# MCU.net
KiCad netlist of a schematic drawn in Altium Designer
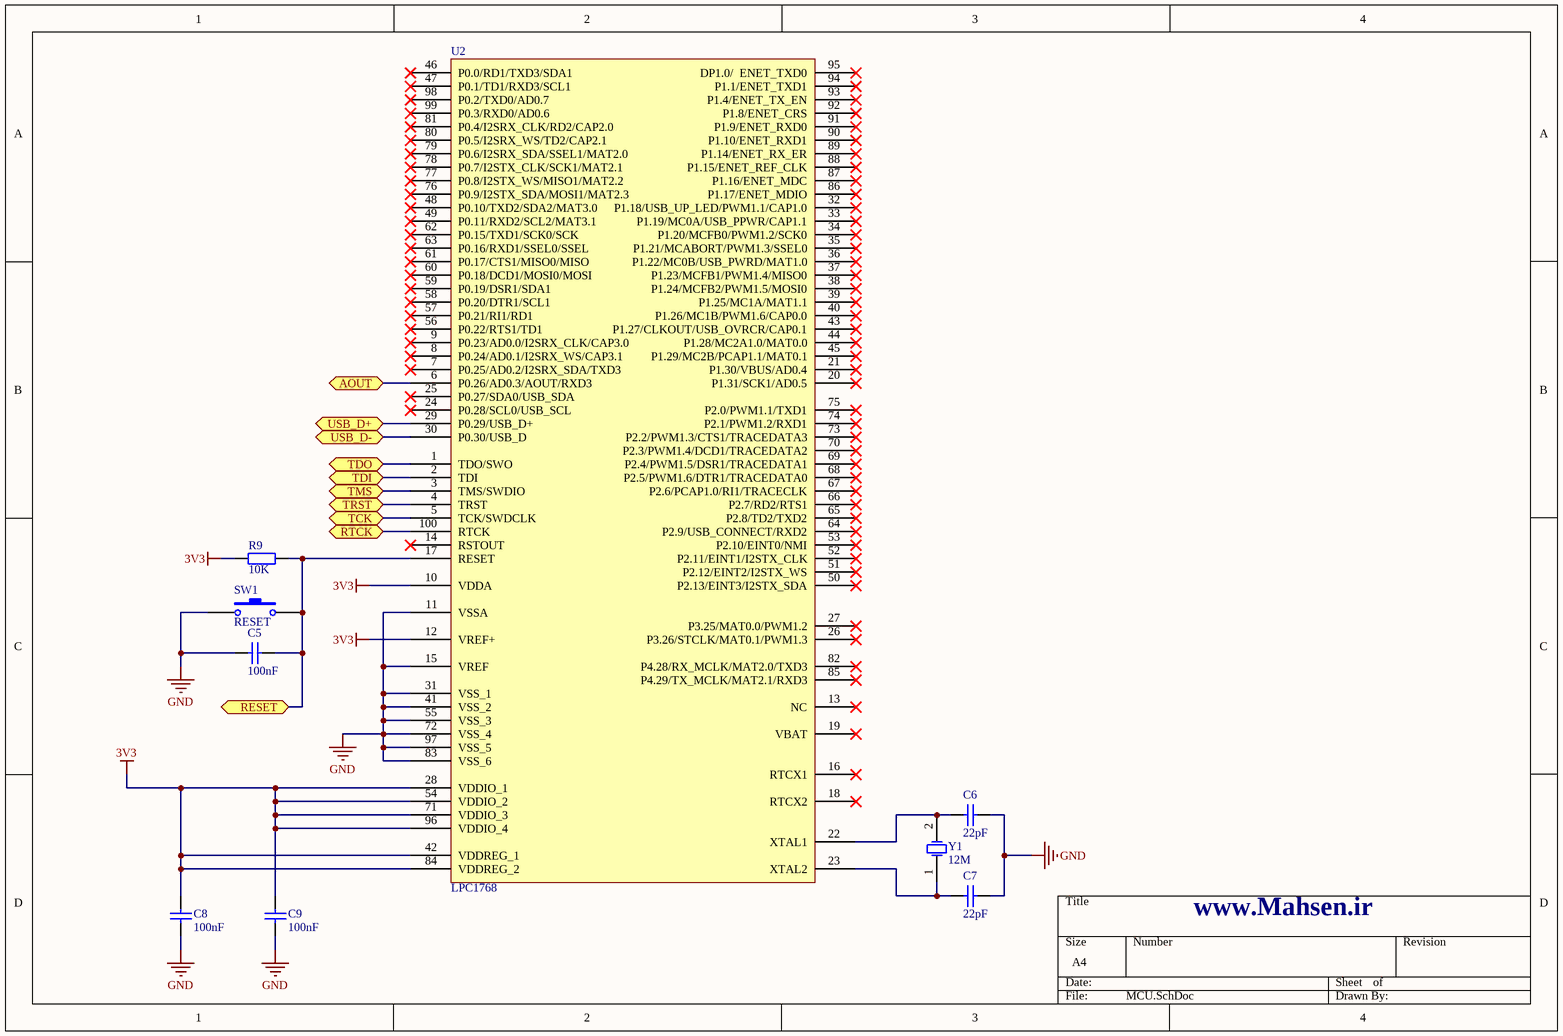
[diagram p0: MCU.SchDoc]

(export (version "E")
  (design (tool "Eeschema 10.0.6"))
  (components
    (comp (ref "C5")
      (value "100nF")
      (footprint "0805")
      (description "Capacitor")
      (fields (field (name "PUBLISHER") "Altium Limited"))
      (libsource (lib "Miscellaneous Devices") (part "Cap"))
    )
    (comp (ref "C6")
      (value "22pF")
      (footprint "0805")
      (description "Capacitor")
      (fields (field (name "PUBLISHER") "Altium Limited"))
      (libsource (lib "Miscellaneous Devices") (part "Cap"))
    )
    (comp (ref "C7")
      (value "22pF")
      (footprint "0805")
      (description "Capacitor")
      (fields (field (name "PUBLISHER") "Altium Limited"))
      (libsource (lib "Miscellaneous Devices") (part "Cap"))
    )
    (comp (ref "C8")
      (value "100nF")
      (footprint "0805")
      (description "Capacitor")
      (fields (field (name "PUBLISHER") "Altium Limited"))
      (libsource (lib "Miscellaneous Devices") (part "Cap"))
    )
    (comp (ref "C9")
      (value "100nF")
      (footprint "0805")
      (description "Capacitor")
      (fields (field (name "PUBLISHER") "Altium Limited"))
      (libsource (lib "Miscellaneous Devices") (part "Cap"))
    )
    (comp (ref "R9")
      (value "10K")
      (footprint "0805")
      (description "Resistor")
      (fields (field (name "PUBLISHER") "Altium Limited"))
      (libsource (lib "Miscellaneous Devices") (part "Res2"))
    )
    (comp (ref "SW1")
      (value "RESET")
      (footprint "SPST-2")
      (description "Switch")
      (fields (field (name "PUBLISHER") "Altium Limited"))
      (libsource (lib "Miscellaneous Devices") (part "SW-PB"))
    )
    (comp (ref "U2") (value "LPC1768") (footprint "LQFP_100") (libsource (lib "Lotfi") (part "LPC1768")))
    (comp (ref "Y1")
      (value "12M")
      (footprint "XTALA")
      (description "Crystal Oscillator")
      (fields (field (name "PUBLISHER") "Altium Limited"))
      (libsource (lib "Miscellaneous Devices") (part "XTAL"))
    )
  )
  (nets
    (net (code "1") (name "/AOUT") (class "Default")
      (node (ref "U2") (pin "6") (pinfunction "P0.26/AD0.3/AOUT/RXD3_6") (pintype "passive"))
    )
    (net (code "2") (name "/RESET") (class "Default")
      (node (ref "C5") (pin "1") (pinfunction "1_1") (pintype "passive"))
      (node (ref "R9") (pin "2") (pinfunction "2_2") (pintype "passive"))
      (node (ref "SW1") (pin "2") (pinfunction "2_2") (pintype "passive"))
      (node (ref "U2") (pin "17") (pinfunction "RESET_17") (pintype "passive"))
    )
    (net (code "3") (name "/RTCK") (class "Default")
      (node (ref "U2") (pin "100") (pinfunction "RTCK_100") (pintype "passive"))
    )
    (net (code "4") (name "/TCK") (class "Default")
      (node (ref "U2") (pin "5") (pinfunction "TCK/SWDCLK_5") (pintype "passive"))
    )
    (net (code "5") (name "/TDI") (class "Default")
      (node (ref "U2") (pin "2") (pinfunction "TDI_2") (pintype "passive"))
    )
    (net (code "6") (name "/TDO") (class "Default")
      (node (ref "U2") (pin "1") (pinfunction "TDO/SWO_1") (pintype "passive"))
    )
    (net (code "7") (name "/TMS") (class "Default")
      (node (ref "U2") (pin "3") (pinfunction "TMS/SWDIO_3") (pintype "passive"))
    )
    (net (code "8") (name "/TRST") (class "Default")
      (node (ref "U2") (pin "4") (pinfunction "TRST_4") (pintype "passive"))
    )
    (net (code "9") (name "/USB_D+") (class "Default")
      (node (ref "U2") (pin "29") (pinfunction "P0.29/USB_D+_29") (pintype "passive"))
    )
    (net (code "10") (name "/USB_D-") (class "Default")
      (node (ref "U2") (pin "30") (pinfunction "P0.30/USB_D_30") (pintype "passive"))
    )
    (net (code "11") (name "3V3") (class "Default")
      (node (ref "C8") (pin "1") (pinfunction "1_1") (pintype "passive"))
      (node (ref "C9") (pin "1") (pinfunction "1_1") (pintype "passive"))
      (node (ref "R9") (pin "1") (pinfunction "1_1") (pintype "passive"))
      (node (ref "U2") (pin "10") (pinfunction "VDDA_10") (pintype "passive"))
      (node (ref "U2") (pin "12") (pinfunction "VREF+_12") (pintype "passive"))
      (node (ref "U2") (pin "28") (pinfunction "VDDIO_1_28") (pintype "passive"))
      (node (ref "U2") (pin "42") (pinfunction "VDDREG_1_42") (pintype "passive"))
      (node (ref "U2") (pin "54") (pinfunction "VDDIO_2_54") (pintype "passive"))
      (node (ref "U2") (pin "71") (pinfunction "VDDIO_3_71") (pintype "passive"))
      (node (ref "U2") (pin "84") (pinfunction "VDDREG_2_84") (pintype "passive"))
      (node (ref "U2") (pin "96") (pinfunction "VDDIO_4_96") (pintype "passive"))
    )
    (net (code "12") (name "GND") (class "Default")
      (node (ref "C5") (pin "2") (pinfunction "2_2") (pintype "passive"))
      (node (ref "C6") (pin "2") (pinfunction "2_2") (pintype "passive"))
      (node (ref "C7") (pin "1") (pinfunction "1_1") (pintype "passive"))
      (node (ref "C8") (pin "2") (pinfunction "2_2") (pintype "passive"))
      (node (ref "C9") (pin "2") (pinfunction "2_2") (pintype "passive"))
      (node (ref "SW1") (pin "1") (pinfunction "1_1") (pintype "passive"))
      (node (ref "U2") (pin "11") (pinfunction "VSSA_11") (pintype "passive"))
      (node (ref "U2") (pin "15") (pinfunction "VREF_15") (pintype "passive"))
      (node (ref "U2") (pin "31") (pinfunction "VSS_1_31") (pintype "passive"))
      (node (ref "U2") (pin "41") (pinfunction "VSS_2_41") (pintype "passive"))
      (node (ref "U2") (pin "55") (pinfunction "VSS_3_55") (pintype "passive"))
      (node (ref "U2") (pin "72") (pinfunction "VSS_4_72") (pintype "passive"))
      (node (ref "U2") (pin "83") (pinfunction "VSS_6_83") (pintype "passive"))
      (node (ref "U2") (pin "97") (pinfunction "VSS_5_97") (pintype "passive"))
    )
    (net (code "13") (name "Net-(U2-XTAL1)") (class "Default")
      (node (ref "C6") (pin "1") (pinfunction "1_1") (pintype "passive"))
      (node (ref "U2") (pin "22") (pinfunction "XTAL1_22") (pintype "passive"))
      (node (ref "Y1") (pin "2") (pinfunction "OSC2_2") (pintype "passive"))
    )
    (net (code "14") (name "Net-(U2-XTAL2)") (class "Default")
      (node (ref "C7") (pin "2") (pinfunction "2_2") (pintype "passive"))
      (node (ref "U2") (pin "23") (pinfunction "XTAL2_23") (pintype "passive"))
      (node (ref "Y1") (pin "1") (pinfunction "OSC1_1") (pintype "passive"))
    )
    (net (code "15") (name "unconnected-(U2-DP1.0{slash}__ENET_TXD0-Pad95)") (class "Default")
      (node (ref "U2") (pin "95") (pinfunction "DP1.0/__ENET_TXD0_95") (pintype "passive+no_connect"))
    )
    (net (code "16") (name "unconnected-(U2-NC-Pad13)") (class "Default")
      (node (ref "U2") (pin "13") (pinfunction "NC_13") (pintype "passive+no_connect"))
    )
    (net (code "17") (name "unconnected-(U2-P0.0{slash}RD1{slash}TXD3{slash}SDA1-Pad46)") (class "Default")
      (node (ref "U2") (pin "46") (pinfunction "P0.0/RD1/TXD3/SDA1_46") (pintype "passive+no_connect"))
    )
    (net (code "18") (name "unconnected-(U2-P0.1{slash}TD1{slash}RXD3{slash}SCL1-Pad47)") (class "Default")
      (node (ref "U2") (pin "47") (pinfunction "P0.1/TD1/RXD3/SCL1_47") (pintype "passive+no_connect"))
    )
    (net (code "19") (name "unconnected-(U2-P0.2{slash}TXD0{slash}AD0.7-Pad98)") (class "Default")
      (node (ref "U2") (pin "98") (pinfunction "P0.2/TXD0/AD0.7_98") (pintype "passive+no_connect"))
    )
    (net (code "20") (name "unconnected-(U2-P0.3{slash}RXD0{slash}AD0.6-Pad99)") (class "Default")
      (node (ref "U2") (pin "99") (pinfunction "P0.3/RXD0/AD0.6_99") (pintype "passive+no_connect"))
    )
    (net (code "21") (name "unconnected-(U2-P0.4{slash}I2SRX_CLK{slash}RD2{slash}CAP2.0-Pad81)") (class "Default")
      (node (ref "U2") (pin "81") (pinfunction "P0.4/I2SRX_CLK/RD2/CAP2.0_81") (pintype "passive+no_connect"))
    )
    (net (code "22") (name "unconnected-(U2-P0.5{slash}I2SRX_WS{slash}TD2{slash}CAP2.1-Pad80)") (class "Default")
      (node (ref "U2") (pin "80") (pinfunction "P0.5/I2SRX_WS/TD2/CAP2.1_80") (pintype "passive+no_connect"))
    )
    (net (code "23") (name "unconnected-(U2-P0.6{slash}I2SRX_SDA{slash}SSEL1{slash}MAT2.0-Pad79)") (class "Default")
      (node (ref "U2") (pin "79") (pinfunction "P0.6/I2SRX_SDA/SSEL1/MAT2.0_79") (pintype "passive+no_connect"))
    )
    (net (code "24") (name "unconnected-(U2-P0.7{slash}I2STX_CLK{slash}SCK1{slash}MAT2.1-Pad78)") (class "Default")
      (node (ref "U2") (pin "78") (pinfunction "P0.7/I2STX_CLK/SCK1/MAT2.1_78") (pintype "passive+no_connect"))
    )
    (net (code "25") (name "unconnected-(U2-P0.8{slash}I2STX_WS{slash}MISO1{slash}MAT2.2-Pad77)") (class "Default")
      (node (ref "U2") (pin "77") (pinfunction "P0.8/I2STX_WS/MISO1/MAT2.2_77") (pintype "passive+no_connect"))
    )
    (net (code "26") (name "unconnected-(U2-P0.9{slash}I2STX_SDA{slash}MOSI1{slash}MAT2.3-Pad76)") (class "Default")
      (node (ref "U2") (pin "76") (pinfunction "P0.9/I2STX_SDA/MOSI1/MAT2.3_76") (pintype "passive+no_connect"))
    )
    (net (code "27") (name "unconnected-(U2-P0.10{slash}TXD2{slash}SDA2{slash}MAT3.0-Pad48)") (class "Default")
      (node (ref "U2") (pin "48") (pinfunction "P0.10/TXD2/SDA2/MAT3.0_48") (pintype "passive+no_connect"))
    )
    (net (code "28") (name "unconnected-(U2-P0.11{slash}RXD2{slash}SCL2{slash}MAT3.1-Pad49)") (class "Default")
      (node (ref "U2") (pin "49") (pinfunction "P0.11/RXD2/SCL2/MAT3.1_49") (pintype "passive+no_connect"))
    )
    (net (code "29") (name "unconnected-(U2-P0.15{slash}TXD1{slash}SCK0{slash}SCK-Pad62)") (class "Default")
      (node (ref "U2") (pin "62") (pinfunction "P0.15/TXD1/SCK0/SCK_62") (pintype "passive+no_connect"))
    )
    (net (code "30") (name "unconnected-(U2-P0.16{slash}RXD1{slash}SSEL0{slash}SSEL-Pad63)") (class "Default")
      (node (ref "U2") (pin "63") (pinfunction "P0.16/RXD1/SSEL0/SSEL_63") (pintype "passive+no_connect"))
    )
    (net (code "31") (name "unconnected-(U2-P0.17{slash}CTS1{slash}MISO0{slash}MISO-Pad61)") (class "Default")
      (node (ref "U2") (pin "61") (pinfunction "P0.17/CTS1/MISO0/MISO_61") (pintype "passive+no_connect"))
    )
    (net (code "32") (name "unconnected-(U2-P0.18{slash}DCD1{slash}MOSI0{slash}MOSI-Pad60)") (class "Default")
      (node (ref "U2") (pin "60") (pinfunction "P0.18/DCD1/MOSI0/MOSI_60") (pintype "passive+no_connect"))
    )
    (net (code "33") (name "unconnected-(U2-P0.19{slash}DSR1{slash}SDA1-Pad59)") (class "Default")
      (node (ref "U2") (pin "59") (pinfunction "P0.19/DSR1/SDA1_59") (pintype "passive+no_connect"))
    )
    (net (code "34") (name "unconnected-(U2-P0.20{slash}DTR1{slash}SCL1-Pad58)") (class "Default")
      (node (ref "U2") (pin "58") (pinfunction "P0.20/DTR1/SCL1_58") (pintype "passive+no_connect"))
    )
    (net (code "35") (name "unconnected-(U2-P0.21{slash}RI1{slash}RD1-Pad57)") (class "Default")
      (node (ref "U2") (pin "57") (pinfunction "P0.21/RI1/RD1_57") (pintype "passive+no_connect"))
    )
    (net (code "36") (name "unconnected-(U2-P0.22{slash}RTS1{slash}TD1-Pad56)") (class "Default")
      (node (ref "U2") (pin "56") (pinfunction "P0.22/RTS1/TD1_56") (pintype "passive+no_connect"))
    )
    (net (code "37") (name "unconnected-(U2-P0.23{slash}AD0.0{slash}I2SRX_CLK{slash}CAP3.0-Pad9)") (class "Default")
      (node (ref "U2") (pin "9") (pinfunction "P0.23/AD0.0/I2SRX_CLK/CAP3.0_9") (pintype "passive+no_connect"))
    )
    (net (code "38") (name "unconnected-(U2-P0.24{slash}AD0.1{slash}I2SRX_WS{slash}CAP3.1-Pad8)") (class "Default")
      (node (ref "U2") (pin "8") (pinfunction "P0.24/AD0.1/I2SRX_WS/CAP3.1_8") (pintype "passive+no_connect"))
    )
    (net (code "39") (name "unconnected-(U2-P0.25{slash}AD0.2{slash}I2SRX_SDA{slash}TXD3-Pad7)") (class "Default")
      (node (ref "U2") (pin "7") (pinfunction "P0.25/AD0.2/I2SRX_SDA/TXD3_7") (pintype "passive+no_connect"))
    )
    (net (code "40") (name "unconnected-(U2-P0.27{slash}SDA0{slash}USB_SDA-Pad25)") (class "Default")
      (node (ref "U2") (pin "25") (pinfunction "P0.27/SDA0/USB_SDA_25") (pintype "passive+no_connect"))
    )
    (net (code "41") (name "unconnected-(U2-P0.28{slash}SCL0{slash}USB_SCL-Pad24)") (class "Default")
      (node (ref "U2") (pin "24") (pinfunction "P0.28/SCL0/USB_SCL_24") (pintype "passive+no_connect"))
    )
    (net (code "42") (name "unconnected-(U2-P1.1{slash}ENET_TXD1-Pad94)") (class "Default")
      (node (ref "U2") (pin "94") (pinfunction "P1.1/ENET_TXD1_94") (pintype "passive+no_connect"))
    )
    (net (code "43") (name "unconnected-(U2-P1.4{slash}ENET_TX_EN-Pad93)") (class "Default")
      (node (ref "U2") (pin "93") (pinfunction "P1.4/ENET_TX_EN_93") (pintype "passive+no_connect"))
    )
    (net (code "44") (name "unconnected-(U2-P1.8{slash}ENET_CRS-Pad92)") (class "Default")
      (node (ref "U2") (pin "92") (pinfunction "P1.8/ENET_CRS_92") (pintype "passive+no_connect"))
    )
    (net (code "45") (name "unconnected-(U2-P1.9{slash}ENET_RXD0-Pad91)") (class "Default")
      (node (ref "U2") (pin "91") (pinfunction "P1.9/ENET_RXD0_91") (pintype "passive+no_connect"))
    )
    (net (code "46") (name "unconnected-(U2-P1.10{slash}ENET_RXD1-Pad90)") (class "Default")
      (node (ref "U2") (pin "90") (pinfunction "P1.10/ENET_RXD1_90") (pintype "passive+no_connect"))
    )
    (net (code "47") (name "unconnected-(U2-P1.14{slash}ENET_RX_ER-Pad89)") (class "Default")
      (node (ref "U2") (pin "89") (pinfunction "P1.14/ENET_RX_ER_89") (pintype "passive+no_connect"))
    )
    (net (code "48") (name "unconnected-(U2-P1.15{slash}ENET_REF_CLK-Pad88)") (class "Default")
      (node (ref "U2") (pin "88") (pinfunction "P1.15/ENET_REF_CLK_88") (pintype "passive+no_connect"))
    )
    (net (code "49") (name "unconnected-(U2-P1.16{slash}ENET_MDC-Pad87)") (class "Default")
      (node (ref "U2") (pin "87") (pinfunction "P1.16/ENET_MDC_87") (pintype "passive+no_connect"))
    )
    (net (code "50") (name "unconnected-(U2-P1.17{slash}ENET_MDIO-Pad86)") (class "Default")
      (node (ref "U2") (pin "86") (pinfunction "P1.17/ENET_MDIO_86") (pintype "passive+no_connect"))
    )
    (net (code "51") (name "unconnected-(U2-P1.18{slash}USB_UP_LED{slash}PWM1.1{slash}CAP1.0-Pad32)") (class "Default")
      (node (ref "U2") (pin "32") (pinfunction "P1.18/USB_UP_LED/PWM1.1/CAP1.0_32") (pintype "passive+no_connect"))
    )
    (net (code "52") (name "unconnected-(U2-P1.19{slash}MC0A{slash}USB_PPWR{slash}CAP1.1-Pad33)") (class "Default")
      (node (ref "U2") (pin "33") (pinfunction "P1.19/MC0A/USB_PPWR/CAP1.1_33") (pintype "passive+no_connect"))
    )
    (net (code "53") (name "unconnected-(U2-P1.20{slash}MCFB0{slash}PWM1.2{slash}SCK0-Pad34)") (class "Default")
      (node (ref "U2") (pin "34") (pinfunction "P1.20/MCFB0/PWM1.2/SCK0_34") (pintype "passive+no_connect"))
    )
    (net (code "54") (name "unconnected-(U2-P1.21{slash}MCABORT{slash}PWM1.3{slash}SSEL0-Pad35)") (class "Default")
      (node (ref "U2") (pin "35") (pinfunction "P1.21/MCABORT/PWM1.3/SSEL0_35") (pintype "passive+no_connect"))
    )
    (net (code "55") (name "unconnected-(U2-P1.22{slash}MC0B{slash}USB_PWRD{slash}MAT1.0-Pad36)") (class "Default")
      (node (ref "U2") (pin "36") (pinfunction "P1.22/MC0B/USB_PWRD/MAT1.0_36") (pintype "passive+no_connect"))
    )
    (net (code "56") (name "unconnected-(U2-P1.23{slash}MCFB1{slash}PWM1.4{slash}MISO0-Pad37)") (class "Default")
      (node (ref "U2") (pin "37") (pinfunction "P1.23/MCFB1/PWM1.4/MISO0_37") (pintype "passive+no_connect"))
    )
    (net (code "57") (name "unconnected-(U2-P1.24{slash}MCFB2{slash}PWM1.5{slash}MOSI0-Pad38)") (class "Default")
      (node (ref "U2") (pin "38") (pinfunction "P1.24/MCFB2/PWM1.5/MOSI0_38") (pintype "passive+no_connect"))
    )
    (net (code "58") (name "unconnected-(U2-P1.25{slash}MC1A{slash}MAT1.1-Pad39)") (class "Default")
      (node (ref "U2") (pin "39") (pinfunction "P1.25/MC1A/MAT1.1_39") (pintype "passive+no_connect"))
    )
    (net (code "59") (name "unconnected-(U2-P1.26{slash}MC1B{slash}PWM1.6{slash}CAP0.0-Pad40)") (class "Default")
      (node (ref "U2") (pin "40") (pinfunction "P1.26/MC1B/PWM1.6/CAP0.0_40") (pintype "passive+no_connect"))
    )
    (net (code "60") (name "unconnected-(U2-P1.27{slash}CLKOUT{slash}USB_OVRCR{slash}CAP0.1-Pad43)") (class "Default")
      (node (ref "U2") (pin "43") (pinfunction "P1.27/CLKOUT/USB_OVRCR/CAP0.1_43") (pintype "passive+no_connect"))
    )
    (net (code "61") (name "unconnected-(U2-P1.28{slash}MC2A1.0{slash}MAT0.0-Pad44)") (class "Default")
      (node (ref "U2") (pin "44") (pinfunction "P1.28/MC2A1.0/MAT0.0_44") (pintype "passive+no_connect"))
    )
    (net (code "62") (name "unconnected-(U2-P1.29{slash}MC2B{slash}PCAP1.1{slash}MAT0.1-Pad45)") (class "Default")
      (node (ref "U2") (pin "45") (pinfunction "P1.29/MC2B/PCAP1.1/MAT0.1_45") (pintype "passive+no_connect"))
    )
    (net (code "63") (name "unconnected-(U2-P1.30{slash}VBUS{slash}AD0.4-Pad21)") (class "Default")
      (node (ref "U2") (pin "21") (pinfunction "P1.30/VBUS/AD0.4_21") (pintype "passive+no_connect"))
    )
    (net (code "64") (name "unconnected-(U2-P1.31{slash}SCK1{slash}AD0.5-Pad20)") (class "Default")
      (node (ref "U2") (pin "20") (pinfunction "P1.31/SCK1/AD0.5_20") (pintype "passive+no_connect"))
    )
    (net (code "65") (name "unconnected-(U2-P2.0{slash}PWM1.1{slash}TXD1-Pad75)") (class "Default")
      (node (ref "U2") (pin "75") (pinfunction "P2.0/PWM1.1/TXD1_75") (pintype "passive+no_connect"))
    )
    (net (code "66") (name "unconnected-(U2-P2.1{slash}PWM1.2{slash}RXD1-Pad74)") (class "Default")
      (node (ref "U2") (pin "74") (pinfunction "P2.1/PWM1.2/RXD1_74") (pintype "passive+no_connect"))
    )
    (net (code "67") (name "unconnected-(U2-P2.2{slash}PWM1.3{slash}CTS1{slash}TRACEDATA3-Pad73)") (class "Default")
      (node (ref "U2") (pin "73") (pinfunction "P2.2/PWM1.3/CTS1/TRACEDATA3_73") (pintype "passive+no_connect"))
    )
    (net (code "68") (name "unconnected-(U2-P2.3{slash}PWM1.4{slash}DCD1{slash}TRACEDATA2-Pad70)") (class "Default")
      (node (ref "U2") (pin "70") (pinfunction "P2.3/PWM1.4/DCD1/TRACEDATA2_70") (pintype "passive+no_connect"))
    )
    (net (code "69") (name "unconnected-(U2-P2.4{slash}PWM1.5{slash}DSR1{slash}TRACEDATA1-Pad69)") (class "Default")
      (node (ref "U2") (pin "69") (pinfunction "P2.4/PWM1.5/DSR1/TRACEDATA1_69") (pintype "passive+no_connect"))
    )
    (net (code "70") (name "unconnected-(U2-P2.5{slash}PWM1.6{slash}DTR1{slash}TRACEDATA0-Pad68)") (class "Default")
      (node (ref "U2") (pin "68") (pinfunction "P2.5/PWM1.6/DTR1/TRACEDATA0_68") (pintype "passive+no_connect"))
    )
    (net (code "71") (name "unconnected-(U2-P2.6{slash}PCAP1.0{slash}RI1{slash}TRACECLK-Pad67)") (class "Default")
      (node (ref "U2") (pin "67") (pinfunction "P2.6/PCAP1.0/RI1/TRACECLK_67") (pintype "passive+no_connect"))
    )
    (net (code "72") (name "unconnected-(U2-P2.7{slash}RD2{slash}RTS1-Pad66)") (class "Default")
      (node (ref "U2") (pin "66") (pinfunction "P2.7/RD2/RTS1_66") (pintype "passive+no_connect"))
    )
    (net (code "73") (name "unconnected-(U2-P2.8{slash}TD2{slash}TXD2-Pad65)") (class "Default")
      (node (ref "U2") (pin "65") (pinfunction "P2.8/TD2/TXD2_65") (pintype "passive+no_connect"))
    )
    (net (code "74") (name "unconnected-(U2-P2.9{slash}USB_CONNECT{slash}RXD2-Pad64)") (class "Default")
      (node (ref "U2") (pin "64") (pinfunction "P2.9/USB_CONNECT/RXD2_64") (pintype "passive+no_connect"))
    )
    (net (code "75") (name "unconnected-(U2-P2.10{slash}EINT0{slash}NMI-Pad53)") (class "Default")
      (node (ref "U2") (pin "53") (pinfunction "P2.10/EINT0/NMI_53") (pintype "passive+no_connect"))
    )
    (net (code "76") (name "unconnected-(U2-P2.11{slash}EINT1{slash}I2STX_CLK-Pad52)") (class "Default")
      (node (ref "U2") (pin "52") (pinfunction "P2.11/EINT1/I2STX_CLK_52") (pintype "passive+no_connect"))
    )
    (net (code "77") (name "unconnected-(U2-P2.12{slash}EINT2{slash}I2STX_WS-Pad51)") (class "Default")
      (node (ref "U2") (pin "51") (pinfunction "P2.12/EINT2/I2STX_WS_51") (pintype "passive+no_connect"))
    )
    (net (code "78") (name "unconnected-(U2-P2.13{slash}EINT3{slash}I2STX_SDA-Pad50)") (class "Default")
      (node (ref "U2") (pin "50") (pinfunction "P2.13/EINT3/I2STX_SDA_50") (pintype "passive+no_connect"))
    )
    (net (code "79") (name "unconnected-(U2-P3.25{slash}MAT0.0{slash}PWM1.2-Pad27)") (class "Default")
      (node (ref "U2") (pin "27") (pinfunction "P3.25/MAT0.0/PWM1.2_27") (pintype "passive+no_connect"))
    )
    (net (code "80") (name "unconnected-(U2-P3.26{slash}STCLK{slash}MAT0.1{slash}PWM1.3-Pad26)") (class "Default")
      (node (ref "U2") (pin "26") (pinfunction "P3.26/STCLK/MAT0.1/PWM1.3_26") (pintype "passive+no_connect"))
    )
    (net (code "81") (name "unconnected-(U2-P4.28{slash}RX_MCLK{slash}MAT2.0{slash}TXD3-Pad82)") (class "Default")
      (node (ref "U2") (pin "82") (pinfunction "P4.28/RX_MCLK/MAT2.0/TXD3_82") (pintype "passive+no_connect"))
    )
    (net (code "82") (name "unconnected-(U2-P4.29{slash}TX_MCLK{slash}MAT2.1{slash}RXD3-Pad85)") (class "Default")
      (node (ref "U2") (pin "85") (pinfunction "P4.29/TX_MCLK/MAT2.1/RXD3_85") (pintype "passive+no_connect"))
    )
    (net (code "83") (name "unconnected-(U2-RSTOUT-Pad14)") (class "Default")
      (node (ref "U2") (pin "14") (pinfunction "RSTOUT_14") (pintype "passive+no_connect"))
    )
    (net (code "84") (name "unconnected-(U2-RTCX1-Pad16)") (class "Default")
      (node (ref "U2") (pin "16") (pinfunction "RTCX1_16") (pintype "passive+no_connect"))
    )
    (net (code "85") (name "unconnected-(U2-RTCX2-Pad18)") (class "Default")
      (node (ref "U2") (pin "18") (pinfunction "RTCX2_18") (pintype "passive+no_connect"))
    )
    (net (code "86") (name "unconnected-(U2-VBAT-Pad19)") (class "Default")
      (node (ref "U2") (pin "19") (pinfunction "VBAT_19") (pintype "passive+no_connect"))
    )
  )
)
